# Adapter-LVLShifterV04.net
KiCad netlist of a schematic drawn in EAGLE
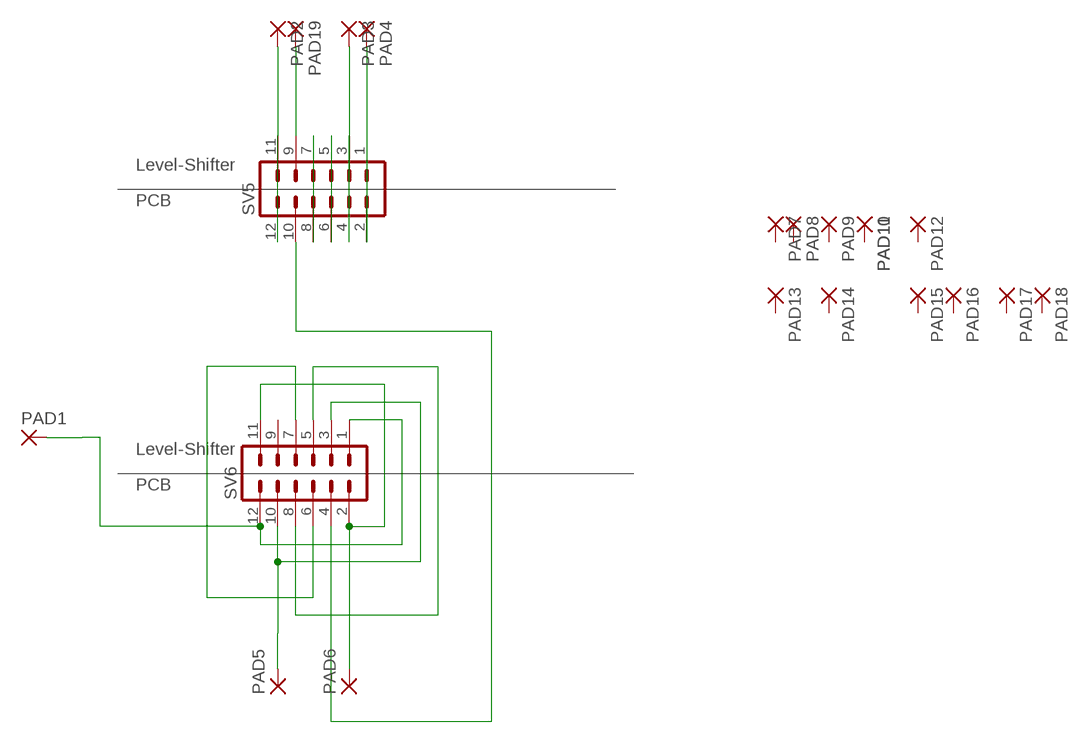
[diagram p0: schematic, sheet 1]

(export (version "E")
  (design (tool "Eeschema 10.0.6"))
  (components
    (comp (ref "PAD1")
      (value "1,6/0,8")
      (footprint "eagle-import:1,6_0,8")
      (libsource (lib "eagle-import") (part "1,6/0,8"))
    )
    (comp (ref "PAD2")
      (value "1,6/0,8")
      (footprint "eagle-import:1,6_0,8")
      (libsource (lib "eagle-import") (part "1,6/0,8"))
    )
    (comp (ref "PAD3")
      (value "1,6/0,8")
      (footprint "eagle-import:1,6_0,8")
      (libsource (lib "eagle-import") (part "1,6/0,8"))
    )
    (comp (ref "PAD4")
      (value "1,6/0,8")
      (footprint "eagle-import:1,6_0,8")
      (libsource (lib "eagle-import") (part "1,6/0,8"))
    )
    (comp (ref "PAD5")
      (value "1,6/0,8")
      (footprint "eagle-import:1,6_0,8")
      (libsource (lib "eagle-import") (part "1,6/0,8"))
    )
    (comp (ref "PAD6")
      (value "1,6/0,8")
      (footprint "eagle-import:1,6_0,8")
      (libsource (lib "eagle-import") (part "1,6/0,8"))
    )
    (comp (ref "PAD7")
      (value "1,6/0,8")
      (footprint "eagle-import:1,6_0,8")
      (libsource (lib "eagle-import") (part "1,6/0,8"))
    )
    (comp (ref "PAD8")
      (value "1,6/0,8")
      (footprint "eagle-import:1,6_0,8")
      (libsource (lib "eagle-import") (part "1,6/0,8"))
    )
    (comp (ref "PAD9")
      (value "1,6/0,8")
      (footprint "eagle-import:1,6_0,8")
      (libsource (lib "eagle-import") (part "1,6/0,8"))
    )
    (comp (ref "PAD10")
      (value "1,6/0,8")
      (footprint "eagle-import:1,6_0,8")
      (libsource (lib "eagle-import") (part "1,6/0,8"))
    )
    (comp (ref "PAD11")
      (value "1,6/0,8")
      (footprint "eagle-import:1,6_0,8")
      (libsource (lib "eagle-import") (part "1,6/0,8"))
    )
    (comp (ref "PAD12")
      (value "1,6/0,8")
      (footprint "eagle-import:1,6_0,8")
      (libsource (lib "eagle-import") (part "1,6/0,8"))
    )
    (comp (ref "PAD13")
      (value "1,6/0,8")
      (footprint "eagle-import:1,6_0,8")
      (libsource (lib "eagle-import") (part "1,6/0,8"))
    )
    (comp (ref "PAD14")
      (value "1,6/0,8")
      (footprint "eagle-import:1,6_0,8")
      (libsource (lib "eagle-import") (part "1,6/0,8"))
    )
    (comp (ref "PAD15")
      (value "1,6/0,8")
      (footprint "eagle-import:1,6_0,8")
      (libsource (lib "eagle-import") (part "1,6/0,8"))
    )
    (comp (ref "PAD16")
      (value "1,6/0,8")
      (footprint "eagle-import:1,6_0,8")
      (libsource (lib "eagle-import") (part "1,6/0,8"))
    )
    (comp (ref "PAD17")
      (value "1,6/0,8")
      (footprint "eagle-import:1,6_0,8")
      (libsource (lib "eagle-import") (part "1,6/0,8"))
    )
    (comp (ref "PAD18")
      (value "1,6/0,8")
      (footprint "eagle-import:1,6_0,8")
      (libsource (lib "eagle-import") (part "1,6/0,8"))
    )
    (comp (ref "PAD19")
      (value "1,6/0,8")
      (footprint "eagle-import:1,6_0,8")
      (libsource (lib "eagle-import") (part "1,6/0,8"))
    )
    (comp (ref "SV5")
      (value "MA06-2")
      (footprint "eagle-import:MA06-2")
      (libsource (lib "eagle-import") (part "MA06-2"))
    )
    (comp (ref "SV6")
      (value "MA06-2")
      (footprint "eagle-import:MA06-2")
      (libsource (lib "eagle-import") (part "MA06-2"))
    )
  )
  (nets
    (net (code "1") (name "Net-(PAD1-P)") (class "Default")
      (node (ref "PAD1") (pin "1") (pinfunction "P_1") (pintype "passive"))
      (node (ref "SV6") (pin "1") (pinfunction "1_1") (pintype "passive"))
      (node (ref "SV6") (pin "12") (pinfunction "12_12") (pintype "passive"))
    )
    (net (code "2") (name "Net-(PAD2-P)") (class "Default")
      (node (ref "PAD2") (pin "1") (pinfunction "P_1") (pintype "passive"))
      (node (ref "SV5") (pin "11") (pinfunction "11_11") (pintype "passive"))
      (node (ref "SV5") (pin "12") (pinfunction "12_12") (pintype "passive"))
    )
    (net (code "3") (name "Net-(PAD3-P)") (class "Default")
      (node (ref "PAD3") (pin "1") (pinfunction "P_1") (pintype "passive"))
      (node (ref "SV5") (pin "3") (pinfunction "3_3") (pintype "passive"))
      (node (ref "SV5") (pin "4") (pinfunction "4_4") (pintype "passive"))
    )
    (net (code "4") (name "Net-(PAD4-P)") (class "Default")
      (node (ref "PAD4") (pin "1") (pinfunction "P_1") (pintype "passive"))
      (node (ref "SV5") (pin "1") (pinfunction "1_1") (pintype "passive"))
      (node (ref "SV5") (pin "2") (pinfunction "2_2") (pintype "passive"))
    )
    (net (code "5") (name "Net-(PAD5-P)") (class "Default")
      (node (ref "PAD5") (pin "1") (pinfunction "P_1") (pintype "passive"))
      (node (ref "SV6") (pin "10") (pinfunction "10_10") (pintype "passive"))
      (node (ref "SV6") (pin "3") (pinfunction "3_3") (pintype "passive"))
    )
    (net (code "6") (name "Net-(PAD6-P)") (class "Default")
      (node (ref "PAD6") (pin "1") (pinfunction "P_1") (pintype "passive"))
      (node (ref "SV6") (pin "11") (pinfunction "11_11") (pintype "passive"))
      (node (ref "SV6") (pin "2") (pinfunction "2_2") (pintype "passive"))
    )
    (net (code "7") (name "Net-(PAD10-P)") (class "Default")
      (node (ref "PAD10") (pin "1") (pinfunction "P_1") (pintype "passive"))
      (node (ref "PAD11") (pin "1") (pinfunction "P_1") (pintype "passive"))
    )
    (net (code "8") (name "Net-(PAD19-P)") (class "Default")
      (node (ref "PAD19") (pin "1") (pinfunction "P_1") (pintype "passive"))
      (node (ref "SV5") (pin "9") (pinfunction "9_9") (pintype "passive"))
    )
    (net (code "9") (name "Net-(SV5-Pad5)") (class "Default")
      (node (ref "SV5") (pin "5") (pinfunction "5_5") (pintype "passive"))
      (node (ref "SV5") (pin "6") (pinfunction "6_6") (pintype "passive"))
    )
    (net (code "10") (name "Net-(SV5-Pad7)") (class "Default")
      (node (ref "SV5") (pin "7") (pinfunction "7_7") (pintype "passive"))
      (node (ref "SV5") (pin "8") (pinfunction "8_8") (pintype "passive"))
    )
    (net (code "11") (name "Net-(SV5-Pad10)") (class "Default")
      (node (ref "SV5") (pin "10") (pinfunction "10_10") (pintype "passive"))
      (node (ref "SV6") (pin "4") (pinfunction "4_4") (pintype "passive"))
    )
    (net (code "12") (name "Net-(SV6-Pad5)") (class "Default")
      (node (ref "SV6") (pin "5") (pinfunction "5_5") (pintype "passive"))
      (node (ref "SV6") (pin "8") (pinfunction "8_8") (pintype "passive"))
    )
    (net (code "13") (name "Net-(SV6-Pad6)") (class "Default")
      (node (ref "SV6") (pin "6") (pinfunction "6_6") (pintype "passive"))
      (node (ref "SV6") (pin "7") (pinfunction "7_7") (pintype "passive"))
    )
    (net (code "14") (name "unconnected-(PAD7-P-Pad1)") (class "Default")
      (node (ref "PAD7") (pin "1") (pinfunction "P_1") (pintype "passive"))
    )
    (net (code "15") (name "unconnected-(PAD8-P-Pad1)") (class "Default")
      (node (ref "PAD8") (pin "1") (pinfunction "P_1") (pintype "passive"))
    )
    (net (code "16") (name "unconnected-(PAD9-P-Pad1)") (class "Default")
      (node (ref "PAD9") (pin "1") (pinfunction "P_1") (pintype "passive"))
    )
    (net (code "17") (name "unconnected-(PAD12-P-Pad1)") (class "Default")
      (node (ref "PAD12") (pin "1") (pinfunction "P_1") (pintype "passive"))
    )
    (net (code "18") (name "unconnected-(PAD13-P-Pad1)") (class "Default")
      (node (ref "PAD13") (pin "1") (pinfunction "P_1") (pintype "passive"))
    )
    (net (code "19") (name "unconnected-(PAD14-P-Pad1)") (class "Default")
      (node (ref "PAD14") (pin "1") (pinfunction "P_1") (pintype "passive"))
    )
    (net (code "20") (name "unconnected-(PAD15-P-Pad1)") (class "Default")
      (node (ref "PAD15") (pin "1") (pinfunction "P_1") (pintype "passive"))
    )
    (net (code "21") (name "unconnected-(PAD16-P-Pad1)") (class "Default")
      (node (ref "PAD16") (pin "1") (pinfunction "P_1") (pintype "passive"))
    )
    (net (code "22") (name "unconnected-(PAD17-P-Pad1)") (class "Default")
      (node (ref "PAD17") (pin "1") (pinfunction "P_1") (pintype "passive"))
    )
    (net (code "23") (name "unconnected-(PAD18-P-Pad1)") (class "Default")
      (node (ref "PAD18") (pin "1") (pinfunction "P_1") (pintype "passive"))
    )
    (net (code "24") (name "unconnected-(SV6-Pad9)") (class "Default")
      (node (ref "SV6") (pin "9") (pinfunction "9_9") (pintype "passive"))
    )
  )
)
